# sepic_schem.net
KiCad netlist of a schematic drawn in Altium Designer
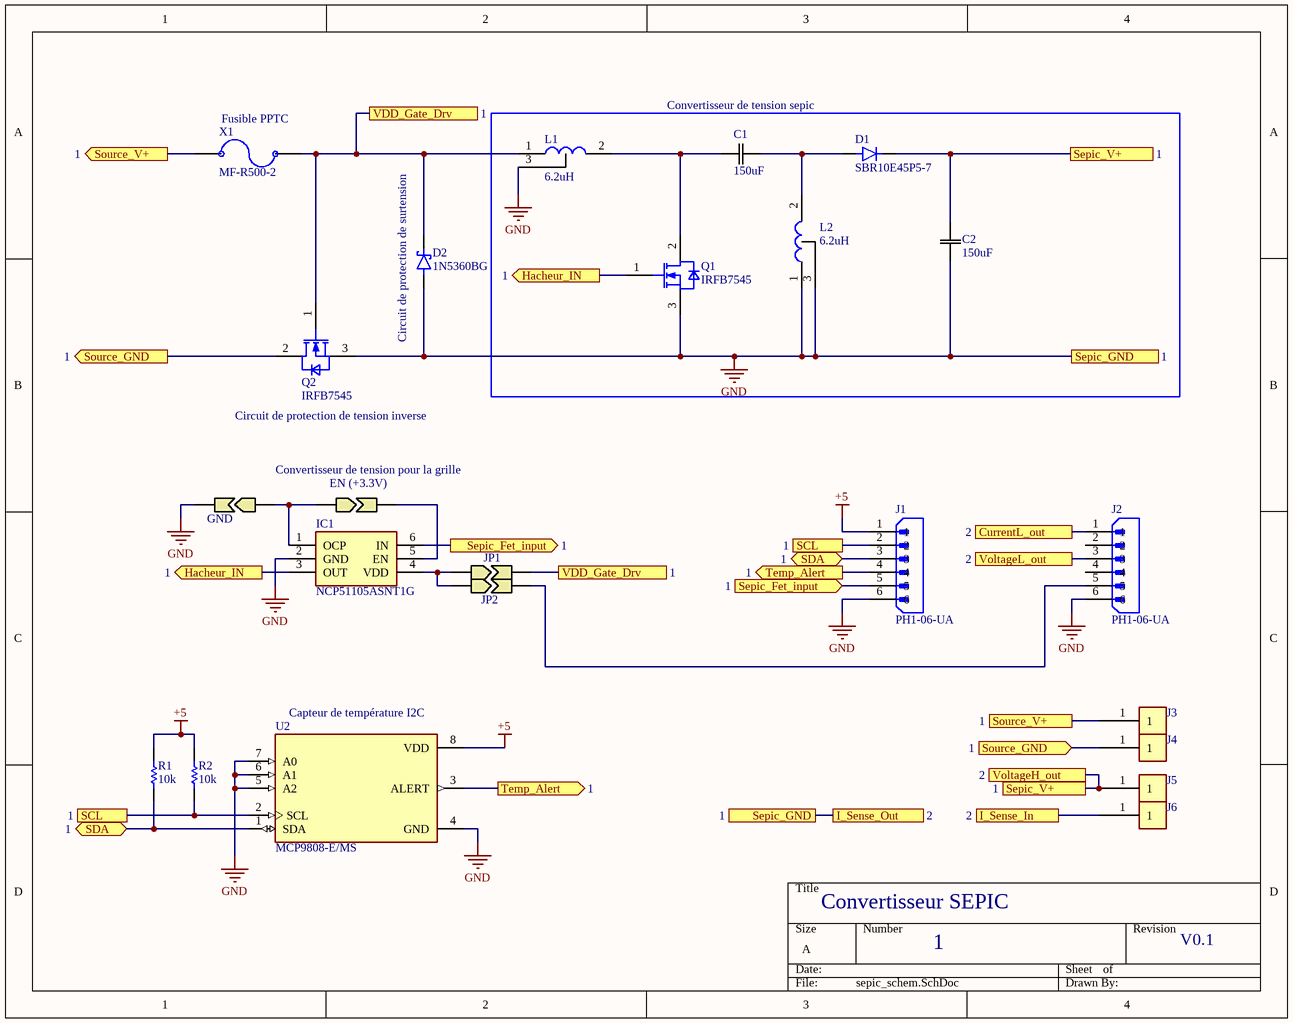
[diagram p0: sepic_schem.SchDoc]

(export (version "E")
  (design (tool "Eeschema 10.0.6"))
  (components
    (comp (ref "C1")
      (value "150uF")
      (footprint "CAP_A768_KEM")
      (description "No Description Available")
      (fields
        (field (name "MANUFACTURER_PART_NUMBER") "A768KS157M1GLAS025")
        (field (name "COPYRIGHT") "Copyright (C) 2025 Ultra Librarian. All rights reserved.")
      )
      (libsource (lib "A25_Projet_conv_CC_Library") (part "A768KS157M1GLAS025"))
    )
    (comp (ref "C2")
      (value "150uF")
      (footprint "CAP_A768_KEM")
      (description "No Description Available")
      (fields
        (field (name "MANUFACTURER_PART_NUMBER") "A768KS157M1GLAS025")
        (field (name "COPYRIGHT") "Copyright (C) 2025 Ultra Librarian. All rights reserved.")
      )
      (libsource (lib "A25_Projet_conv_CC_Library") (part "A768KS157M1GLAS025"))
    )
    (comp (ref "D1")
      (value "SBR10E45P5-7")
      (footprint "SBR10E45P5-7")
      (description "SBR10E45P5-7, low Vf 5W 10A")
      (fields (field (name "MF") "{'manufacturer': u'onsemi'}") (field (name "MP") "1N5360BG"))
      (libsource (lib "A25_Projet_conv_CC_Library") (part "SBR10E45P5-7"))
    )
    (comp (ref "D2")
      (value "1N5360BG")
      (footprint "DIOAD1543W101L863D368")
      (fields (field (name "MF") "{'manufacturer': u'onsemi'}"))
      (libsource (lib "A25_Projet_conv_CC_Library") (part "1N5360BG"))
    )
    (comp (ref "EN (+3.3V)")
      (value "Solder Bridge")
      (footprint "Bridge1mmX2mm")
      (libsource (lib "A25_Projet_conv_CC_Library") (part "Solder Bridge"))
    )
    (comp (ref "GND")
      (value "Solder Bridge")
      (footprint "Bridge1mmX2mm")
      (libsource (lib "A25_Projet_conv_CC_Library") (part "Solder Bridge"))
    )
    (comp (ref "IC1")
      (value "NCP51105ASNT1G")
      (footprint "SOP95P275X110-6N")
      (description "Integrated Circuit")
      (libsource (lib "A25_Projet_conv_CC_Library") (part "NCP51105ASNT1G"))
    )
    (comp (ref "J1")
      (value "PH1-06-UA")
      (footprint "ADAMTECH_PH1-06-UA")
      (description "Pin Header 6P .100 Pitch Plug ¦ Adam Tech PH1-06-UA")
      (fields (field (name "MF") "Adam Tech"))
      (libsource (lib "A25_Projet_conv_CC_Library") (part "PH1-06-UA"))
    )
    (comp (ref "J2")
      (value "PH1-06-UA")
      (footprint "ADAMTECH_PH1-06-UA")
      (description "Pin Header 6P .100 Pitch Plug ¦ Adam Tech PH1-06-UA")
      (fields (field (name "MF") "Adam Tech"))
      (libsource (lib "A25_Projet_conv_CC_Library") (part "PH1-06-UA"))
    )
    (comp (ref "J3")
      (value "BananaConnector")
      (footprint "banana_connector")
      (libsource (lib "A25_Projet_conv_CC_Library") (part "BananaConnector"))
    )
    (comp (ref "J4")
      (value "BananaConnector")
      (footprint "banana_connector")
      (libsource (lib "A25_Projet_conv_CC_Library") (part "BananaConnector"))
    )
    (comp (ref "J5")
      (value "BananaConnector")
      (footprint "banana_connector")
      (libsource (lib "A25_Projet_conv_CC_Library") (part "BananaConnector"))
    )
    (comp (ref "J6")
      (value "BananaConnector")
      (footprint "banana_connector")
      (libsource (lib "A25_Projet_conv_CC_Library") (part "BananaConnector"))
    )
    (comp (ref "JP1")
      (value "Solder Bridge")
      (footprint "Bridge1mmX2mm")
      (libsource (lib "A25_Projet_conv_CC_Library") (part "Solder Bridge"))
    )
    (comp (ref "JP2")
      (value "Solder Bridge")
      (footprint "Bridge1mmX2mm")
      (libsource (lib "A25_Projet_conv_CC_Library") (part "Solder Bridge"))
    )
    (comp (ref "L1")
      (value "6.2uH")
      (footprint "CDEP147NP6R1MC125")
      (description "Inductor")
      (fields
        (field (name "MANUFACTURER_PART_NUMBER") "CDEP147NP-6R1MC-125")
        (field (name "MOUSER PART NUMBER") "851-CDEP147P6R1MC125")
      )
      (libsource (lib "A25_Projet_conv_CC_Library") (part "CDEP147NP-6R1MC-125"))
    )
    (comp (ref "L2")
      (value "6.2uH")
      (footprint "CDEP147NP6R1MC125")
      (description "Inductor")
      (fields
        (field (name "MANUFACTURER_PART_NUMBER") "CDEP147NP-6R1MC-125")
        (field (name "MOUSER PART NUMBER") "851-CDEP147P6R1MC125")
      )
      (libsource (lib "") (part "CDEP147NP-6R1MC-125_1"))
    )
    (comp (ref "Q1")
      (value "IRFB7545")
      (footprint "IFX-PG-TO220-3-904")
      (fields (field (name "MANUFACTURER") "Infineon Technologies"))
      (libsource (lib "A25_Projet_conv_CC_Library") (part "IRFB7545"))
    )
    (comp (ref "Q2")
      (value "IRFB7545")
      (footprint "IFX-PG-TO220-3-904")
      (fields (field (name "MANUFACTURER") "Infineon Technologies"))
      (libsource (lib "A25_Projet_conv_CC_Library") (part "IRFB7545"))
    )
    (comp (ref "R1")
      (value "10k")
      (footprint "AXIAL-0.3")
      (description "Resistor")
      (fields (field (name "Comment") "Res1") (field (name "PUBLISHER") "Altium Limited"))
      (libsource (lib "Miscellaneous Devices") (part "Res1"))
    )
    (comp (ref "R2")
      (value "10k")
      (footprint "AXIAL-0.3")
      (description "Resistor")
      (fields (field (name "Comment") "Res1") (field (name "PUBLISHER") "Altium Limited"))
      (libsource (lib "Miscellaneous Devices") (part "Res1"))
    )
    (comp (ref "U2")
      (value "MCP9808-E/MS")
      (footprint "SOP65P490X110-8N")
      (fields (field (name "MF") "Microchip"))
      (libsource (lib "A25_Projet_conv_CC_Library") (part "MCP9808-E/MS"))
    )
    (comp (ref "X1")
      (value "MF-R500-2")
      (footprint "MF-R500-2")
      (libsource (lib "A25_Projet_conv_CC_Library") (part "MF-R500-2"))
    )
  )
  (nets
    (net (code "1") (name "+5") (class "Default")
      (node (ref "J1") (pin "1") (pinfunction "1_1") (pintype "passive"))
      (node (ref "R1") (pin "2") (pinfunction "2_2") (pintype "passive"))
      (node (ref "R2") (pin "2") (pinfunction "2_2") (pintype "passive"))
      (node (ref "U2") (pin "8") (pinfunction "VDD_8") (pintype "power_in"))
    )
    (net (code "2") (name "/CurrentL_out") (class "Default")
      (node (ref "J2") (pin "1") (pinfunction "1_1") (pintype "passive"))
    )
    (net (code "3") (name "/Hacheur_IN") (class "Default")
      (node (ref "IC1") (pin "3") (pinfunction "OUT_3") (pintype "passive"))
      (node (ref "Q1") (pin "1") (pinfunction "GATE_1") (pintype "passive"))
    )
    (net (code "4") (name "/I_Sense_In") (class "Default")
      (node (ref "J6") (pin "1") (pinfunction "1_1") (pintype "passive"))
    )
    (net (code "5") (name "/SCL") (class "Default")
      (node (ref "J1") (pin "2") (pinfunction "2_2") (pintype "passive"))
      (node (ref "R2") (pin "1") (pinfunction "1_1") (pintype "passive"))
      (node (ref "U2") (pin "2") (pinfunction "SCL_2") (pintype "input"))
    )
    (net (code "6") (name "/SDA") (class "Default")
      (node (ref "J1") (pin "3") (pinfunction "3_3") (pintype "passive"))
      (node (ref "R1") (pin "1") (pinfunction "1_1") (pintype "passive"))
      (node (ref "U2") (pin "1") (pinfunction "SDA_1") (pintype "bidirectional"))
    )
    (net (code "7") (name "/Sepic_Fet_input") (class "Default")
      (node (ref "IC1") (pin "6") (pinfunction "IN_6") (pintype "passive"))
      (node (ref "J1") (pin "5") (pinfunction "5_5") (pintype "passive"))
    )
    (net (code "8") (name "/Sepic_V+") (class "Default")
      (node (ref "C2") (pin "2") (pinfunction "2_2") (pintype "passive"))
      (node (ref "D1") (pin "2") (pinfunction "K_2") (pintype "passive"))
      (node (ref "J5") (pin "1") (pinfunction "1_1") (pintype "passive"))
    )
    (net (code "9") (name "/Source_GND") (class "Default")
      (node (ref "J4") (pin "1") (pinfunction "1_1") (pintype "passive"))
      (node (ref "Q2") (pin "2") (pinfunction "DRAIN_2") (pintype "passive"))
    )
    (net (code "10") (name "/Source_V+") (class "Default")
      (node (ref "J3") (pin "1") (pinfunction "1_1") (pintype "passive"))
      (node (ref "X1") (pin "1") (pinfunction "1_1") (pintype "passive"))
    )
    (net (code "11") (name "/Temp_Alert") (class "Default")
      (node (ref "J1") (pin "4") (pinfunction "4_4") (pintype "passive"))
      (node (ref "U2") (pin "3") (pinfunction "ALERT_3") (pintype "output"))
    )
    (net (code "12") (name "/VDD_Gate_Drv") (class "Default")
      (node (ref "D2") (pin "1") (pinfunction "K_1") (pintype "passive"))
      (node (ref "JP1") (pin "2") (pinfunction "2_2") (pintype "passive"))
      (node (ref "L1") (pin "1") (pinfunction "1_1") (pintype "passive"))
      (node (ref "Q2") (pin "1") (pinfunction "GATE_1") (pintype "passive"))
      (node (ref "X1") (pin "2") (pinfunction "2_2") (pintype "passive"))
    )
    (net (code "13") (name "/VoltageL_out") (class "Default")
      (node (ref "J2") (pin "3") (pinfunction "3_3") (pintype "passive"))
    )
    (net (code "14") (name "GND") (class "Default")
      (node (ref "C2") (pin "1") (pinfunction "1_1") (pintype "passive"))
      (node (ref "D2") (pin "2") (pinfunction "A_2") (pintype "passive"))
      (node (ref "GND") (pin "2") (pinfunction "2_2") (pintype "passive"))
      (node (ref "IC1") (pin "2") (pinfunction "GND_2") (pintype "passive"))
      (node (ref "J1") (pin "6") (pinfunction "6_6") (pintype "passive"))
      (node (ref "J2") (pin "6") (pinfunction "6_6") (pintype "passive"))
      (node (ref "L1") (pin "3") (pinfunction "3_3") (pintype "passive"))
      (node (ref "L2") (pin "1") (pinfunction "1_1") (pintype "passive"))
      (node (ref "L2") (pin "3") (pinfunction "3_3") (pintype "passive"))
      (node (ref "Q1") (pin "3") (pinfunction "SOURCE_3") (pintype "passive"))
      (node (ref "Q2") (pin "3") (pinfunction "SOURCE_3") (pintype "passive"))
      (node (ref "U2") (pin "4") (pinfunction "GND_4") (pintype "power_in"))
      (node (ref "U2") (pin "5") (pinfunction "A2_5") (pintype "input"))
      (node (ref "U2") (pin "6") (pinfunction "A1_6") (pintype "input"))
      (node (ref "U2") (pin "7") (pinfunction "A0_7") (pintype "input"))
    )
    (net (code "15") (name "Net-(D1-A)") (class "Default")
      (node (ref "C1") (pin "2") (pinfunction "2_2") (pintype "passive"))
      (node (ref "D1") (pin "1") (pinfunction "A_1") (pintype "passive"))
      (node (ref "L2") (pin "2") (pinfunction "2_2") (pintype "passive"))
    )
    (net (code "16") (name "Net-(IC1-EN)") (class "Default")
      (node (ref "EN (+3.3V)") (pin "2") (pinfunction "2_2") (pintype "passive"))
      (node (ref "IC1") (pin "5") (pinfunction "EN_5") (pintype "passive"))
    )
    (net (code "17") (name "Net-(IC1-OCP)") (class "Default")
      (node (ref "EN (+3.3V)") (pin "1") (pinfunction "1_1") (pintype "passive"))
      (node (ref "GND") (pin "1") (pinfunction "1_1") (pintype "passive"))
      (node (ref "IC1") (pin "1") (pinfunction "OCP_1") (pintype "passive"))
    )
    (net (code "18") (name "Net-(IC1-VDD)") (class "Default")
      (node (ref "IC1") (pin "4") (pinfunction "VDD_4") (pintype "passive"))
      (node (ref "JP1") (pin "1") (pinfunction "1_1") (pintype "passive"))
      (node (ref "JP2") (pin "1") (pinfunction "1_1") (pintype "passive"))
    )
    (net (code "19") (name "Net-(J2-Pad5)") (class "Default")
      (node (ref "J2") (pin "5") (pinfunction "5_5") (pintype "passive"))
      (node (ref "JP2") (pin "2") (pinfunction "2_2") (pintype "passive"))
    )
    (net (code "20") (name "Net-(Q1-DRAIN)") (class "Default")
      (node (ref "C1") (pin "1") (pinfunction "1_1") (pintype "passive"))
      (node (ref "L1") (pin "2") (pinfunction "2_2") (pintype "passive"))
      (node (ref "Q1") (pin "2") (pinfunction "DRAIN_2") (pintype "passive"))
    )
    (net (code "21") (name "unconnected-(J2-Pad2)") (class "Default")
      (node (ref "J2") (pin "2") (pinfunction "2_2") (pintype "passive"))
    )
    (net (code "22") (name "unconnected-(J2-Pad4)") (class "Default")
      (node (ref "J2") (pin "4") (pinfunction "4_4") (pintype "passive"))
    )
  )
)
